# SmartLamp.net
KiCad netlist of a schematic drawn in EAGLE
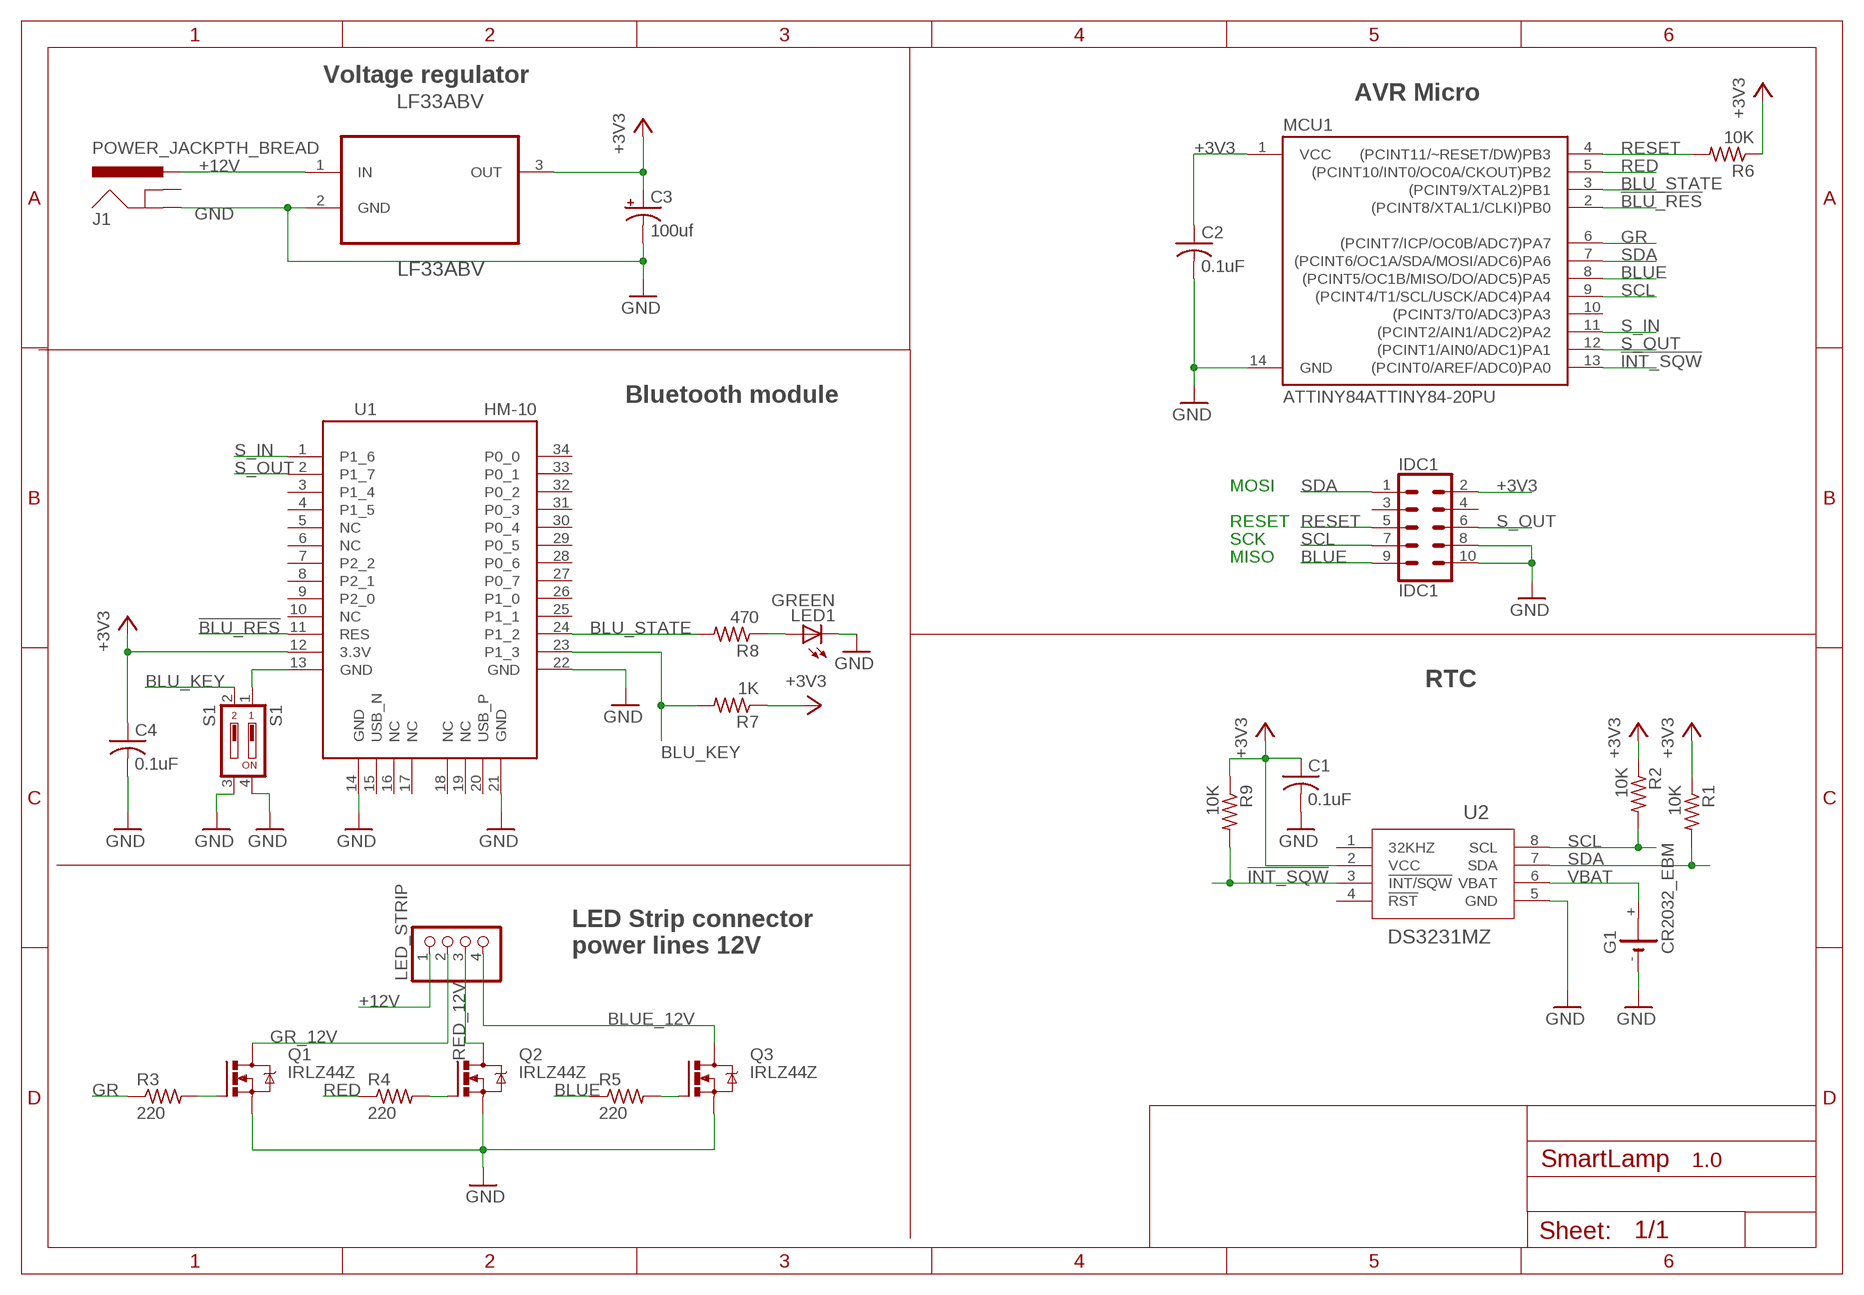
[diagram p0: schematic, sheet 1]

(export (version "E")
  (design (tool "Eeschema 10.0.6"))
  (components
    (comp (ref "C1")
      (value "0.1uF")
      (footprint "eagle-import:C025-024X044")
      (libsource (lib "eagle-import") (part "C-US025-024X044"))
    )
    (comp (ref "C2")
      (value "0.1uF")
      (footprint "eagle-import:C025-024X044")
      (libsource (lib "eagle-import") (part "C-US025-024X044"))
    )
    (comp (ref "C3")
      (value "100uf")
      (footprint "eagle-import:CPOL-RADIAL-10UF-25V")
      (libsource (lib "eagle-import") (part "CAP_POLPTH2"))
    )
    (comp (ref "C4")
      (value "0.1uF")
      (footprint "eagle-import:C025-024X044")
      (libsource (lib "eagle-import") (part "C-US025-024X044"))
    )
    (comp (ref "G1")
      (value "CR2032_EBM")
      (footprint "eagle-import:CR2032_EBM")
      (libsource (lib "eagle-import") (part "CR2032_EBM"))
    )
    (comp (ref "IDC1")
      (value "IDC1")
      (footprint "eagle-import:2X5-SHROUDED")
      (libsource (lib "eagle-import") (part "CONN_05X2SHD"))
    )
    (comp (ref "J1")
      (value "POWER_JACKPTH_BREAD")
      (footprint "eagle-import:POWER_JACK_PTH_BREAD")
      (libsource (lib "eagle-import") (part "POWER_JACKPTH_BREAD"))
    )
    (comp (ref "LED1")
      (value "GREEN")
      (footprint "eagle-import:LED3MM")
      (libsource (lib "eagle-import") (part "LED3MM"))
    )
    (comp (ref "LED_STRIP")
      (value "PINHD-1X4")
      (footprint "eagle-import:1X04")
      (libsource (lib "eagle-import") (part "PINHD-1X4"))
    )
    (comp (ref "LF33ABV")
      (value "LF33ABV")
      (footprint "eagle-import:TO254P450X1020X1935-3P")
      (libsource (lib "eagle-import") (part "LF33ABV"))
    )
    (comp (ref "MCU1")
      (value "ATTINY84ATTINY84-20PU")
      (footprint "eagle-import:DIL14")
      (libsource (lib "eagle-import") (part "ATTINY84ATTINY84-20PU"))
    )
    (comp (ref "Q1")
      (value "IRLZ44Z")
      (footprint "eagle-import:TO220BH")
      (libsource (lib "eagle-import") (part "IRLZ44Z"))
    )
    (comp (ref "Q2")
      (value "IRLZ44Z")
      (footprint "eagle-import:TO220BH")
      (libsource (lib "eagle-import") (part "IRLZ44Z"))
    )
    (comp (ref "Q3")
      (value "IRLZ44Z")
      (footprint "eagle-import:TO220BH")
      (libsource (lib "eagle-import") (part "IRLZ44Z"))
    )
    (comp (ref "R1")
      (value "10K")
      (footprint "eagle-import:0309_12")
      (libsource (lib "eagle-import") (part "R-US_0309/12"))
    )
    (comp (ref "R2")
      (value "10K")
      (footprint "eagle-import:0309_12")
      (libsource (lib "eagle-import") (part "R-US_0309/12"))
    )
    (comp (ref "R3")
      (value "220")
      (footprint "eagle-import:0207_10")
      (libsource (lib "eagle-import") (part "R-US_0207/10"))
    )
    (comp (ref "R4")
      (value "220")
      (footprint "eagle-import:0207_10")
      (libsource (lib "eagle-import") (part "R-US_0207/10"))
    )
    (comp (ref "R5")
      (value "220")
      (footprint "eagle-import:0207_10")
      (libsource (lib "eagle-import") (part "R-US_0207/10"))
    )
    (comp (ref "R6")
      (value "10K")
      (footprint "eagle-import:0309_12")
      (libsource (lib "eagle-import") (part "R-US_0309/12"))
    )
    (comp (ref "R7")
      (value "1K")
      (footprint "eagle-import:0207_10")
      (libsource (lib "eagle-import") (part "R-US_0207/10"))
    )
    (comp (ref "R8")
      (value "470")
      (footprint "eagle-import:0309_12")
      (libsource (lib "eagle-import") (part "R-US_0309/12"))
    )
    (comp (ref "R9")
      (value "10K")
      (footprint "eagle-import:0309_12")
      (libsource (lib "eagle-import") (part "R-US_0309/12"))
    )
    (comp (ref "S1")
      (value "S1")
      (footprint "eagle-import:SD4-02")
      (libsource (lib "eagle-import") (part "SD4-02"))
    )
    (comp (ref "U1")
      (value "HM-10")
      (footprint "eagle-import:HM-10")
      (libsource (lib "eagle-import") (part "HM-10"))
    )
    (comp (ref "U2")
      (value "DS3231MZ")
      (footprint "eagle-import:21-0041B_8")
      (libsource (lib "eagle-import") (part "DS3231MZ"))
    )
  )
  (nets
    (net (code "1") (name "+3V3") (class "Default")
      (node (ref "C1") (pin "1") (pinfunction "1_1") (pintype "passive"))
      (node (ref "C2") (pin "1") (pinfunction "1_1") (pintype "passive"))
      (node (ref "C3") (pin "1") (pinfunction "+_1") (pintype "passive"))
      (node (ref "C4") (pin "1") (pinfunction "1_1") (pintype "passive"))
      (node (ref "IDC1") (pin "2") (pinfunction "2_2") (pintype "passive"))
      (node (ref "LF33ABV") (pin "3") (pinfunction "OUT_3") (pintype "passive"))
      (node (ref "MCU1") (pin "1") (pinfunction "VCC_1") (pintype "bidirectional"))
      (node (ref "R1") (pin "1") (pinfunction "1_1") (pintype "passive"))
      (node (ref "R2") (pin "1") (pinfunction "1_1") (pintype "passive"))
      (node (ref "R6") (pin "1") (pinfunction "1_1") (pintype "passive"))
      (node (ref "R7") (pin "1") (pinfunction "1_1") (pintype "passive"))
      (node (ref "R9") (pin "1") (pinfunction "1_1") (pintype "passive"))
      (node (ref "U1") (pin "12") (pinfunction "3.3V_12") (pintype "bidirectional"))
      (node (ref "U2") (pin "2") (pinfunction "VCC_2") (pintype "power_in"))
    )
    (net (code "2") (name "/+12V") (class "Default")
      (node (ref "J1") (pin "PWR") (pinfunction "PWR_PWR") (pintype "bidirectional"))
      (node (ref "LED_STRIP") (pin "1") (pinfunction "1_1") (pintype "passive"))
      (node (ref "LF33ABV") (pin "1") (pinfunction "IN_1") (pintype "input"))
    )
    (net (code "3") (name "/BLUE") (class "Default")
      (node (ref "IDC1") (pin "9") (pinfunction "9_9") (pintype "passive"))
      (node (ref "MCU1") (pin "8") (pinfunction "(PCINT5/OC1B/MISO/DO/ADC5)PA5_8") (pintype "bidirectional"))
      (node (ref "R5") (pin "1") (pinfunction "1_1") (pintype "passive"))
    )
    (net (code "4") (name "/BLUE_12V") (class "Default")
      (node (ref "LED_STRIP") (pin "4") (pinfunction "4_4") (pintype "passive"))
      (node (ref "Q3") (pin "D") (pinfunction "D_D") (pintype "passive"))
    )
    (net (code "5") (name "/BLU_KEY") (class "Default")
      (node (ref "R7") (pin "2") (pinfunction "2_2") (pintype "passive"))
      (node (ref "S1") (pin "2") (pinfunction "2_2") (pintype "passive"))
      (node (ref "U1") (pin "23") (pinfunction "P1_3_23") (pintype "bidirectional"))
    )
    (net (code "6") (name "/BLU_STATE") (class "Default")
      (node (ref "MCU1") (pin "3") (pinfunction "(PCINT9/XTAL2)PB1_3") (pintype "bidirectional"))
      (node (ref "R8") (pin "2") (pinfunction "2_2") (pintype "passive"))
      (node (ref "U1") (pin "24") (pinfunction "P1_2_24") (pintype "bidirectional"))
    )
    (net (code "7") (name "/GR") (class "Default")
      (node (ref "MCU1") (pin "6") (pinfunction "(PCINT7/ICP/OC0B/ADC7)PA7_6") (pintype "bidirectional"))
      (node (ref "R3") (pin "1") (pinfunction "1_1") (pintype "passive"))
    )
    (net (code "8") (name "/GR_12V") (class "Default")
      (node (ref "LED_STRIP") (pin "2") (pinfunction "2_2") (pintype "passive"))
      (node (ref "Q1") (pin "D") (pinfunction "D_D") (pintype "passive"))
    )
    (net (code "9") (name "/RED") (class "Default")
      (node (ref "MCU1") (pin "5") (pinfunction "(PCINT10/INT0/OC0A/CKOUT)PB2_5") (pintype "bidirectional"))
      (node (ref "R4") (pin "1") (pinfunction "1_1") (pintype "passive"))
    )
    (net (code "10") (name "/RED_12V") (class "Default")
      (node (ref "LED_STRIP") (pin "3") (pinfunction "3_3") (pintype "passive"))
      (node (ref "Q2") (pin "D") (pinfunction "D_D") (pintype "passive"))
    )
    (net (code "11") (name "/RESET") (class "Default")
      (node (ref "IDC1") (pin "5") (pinfunction "5_5") (pintype "passive"))
      (node (ref "MCU1") (pin "4") (pinfunction "(PCINT11/~{RESET/DW})PB3_4") (pintype "bidirectional"))
      (node (ref "R6") (pin "2") (pinfunction "2_2") (pintype "passive"))
    )
    (net (code "12") (name "/SCL") (class "Default")
      (node (ref "IDC1") (pin "7") (pinfunction "7_7") (pintype "passive"))
      (node (ref "MCU1") (pin "9") (pinfunction "(PCINT4/T1/SCL/USCK/ADC4)PA4_9") (pintype "bidirectional"))
      (node (ref "R2") (pin "2") (pinfunction "2_2") (pintype "passive"))
      (node (ref "U2") (pin "8") (pinfunction "SCL_8") (pintype "passive"))
    )
    (net (code "13") (name "/SDA") (class "Default")
      (node (ref "IDC1") (pin "1") (pinfunction "1_1") (pintype "passive"))
      (node (ref "MCU1") (pin "7") (pinfunction "(PCINT6/OC1A/SDA/MOSI/ADC6)PA6_7") (pintype "bidirectional"))
      (node (ref "R1") (pin "2") (pinfunction "2_2") (pintype "passive"))
      (node (ref "U2") (pin "7") (pinfunction "SDA_7") (pintype "passive"))
    )
    (net (code "14") (name "/S_IN") (class "Default")
      (node (ref "MCU1") (pin "11") (pinfunction "(PCINT2/AIN1/ADC2)PA2_11") (pintype "bidirectional"))
      (node (ref "U1") (pin "1") (pinfunction "P1_6_1") (pintype "bidirectional"))
    )
    (net (code "15") (name "/S_OUT") (class "Default")
      (node (ref "IDC1") (pin "6") (pinfunction "6_6") (pintype "passive"))
      (node (ref "MCU1") (pin "12") (pinfunction "(PCINT1/AIN0/ADC1)PA1_12") (pintype "bidirectional"))
      (node (ref "U1") (pin "2") (pinfunction "P1_7_2") (pintype "bidirectional"))
    )
    (net (code "16") (name "/VBAT") (class "Default")
      (node (ref "G1") (pin "+") (pinfunction "+_+") (pintype "passive"))
      (node (ref "U2") (pin "6") (pinfunction "VBAT_6") (pintype "power_in"))
    )
    (net (code "17") (name "/~{BLU_RES}") (class "Default")
      (node (ref "MCU1") (pin "2") (pinfunction "(PCINT8/XTAL1/CLKI)PB0_2") (pintype "bidirectional"))
      (node (ref "U1") (pin "11") (pinfunction "RES_11") (pintype "bidirectional"))
    )
    (net (code "18") (name "/~{INT_SQW}") (class "Default")
      (node (ref "MCU1") (pin "13") (pinfunction "(PCINT0/AREF/ADC0)PA0_13") (pintype "bidirectional"))
      (node (ref "R9") (pin "2") (pinfunction "2_2") (pintype "passive"))
      (node (ref "U2") (pin "3") (pinfunction "~{INT/SQW}_3") (pintype "passive"))
    )
    (net (code "19") (name "GND") (class "Default")
      (node (ref "C1") (pin "2") (pinfunction "2_2") (pintype "passive"))
      (node (ref "C2") (pin "2") (pinfunction "2_2") (pintype "passive"))
      (node (ref "C3") (pin "2") (pinfunction "-_2") (pintype "passive"))
      (node (ref "C4") (pin "2") (pinfunction "2_2") (pintype "passive"))
      (node (ref "G1") (pin "-") (pinfunction "-_-") (pintype "passive"))
      (node (ref "IDC1") (pin "10") (pinfunction "10_10") (pintype "passive"))
      (node (ref "IDC1") (pin "8") (pinfunction "8_8") (pintype "passive"))
      (node (ref "J1") (pin "GND") (pinfunction "GND_GND") (pintype "bidirectional"))
      (node (ref "LED1") (pin "K") (pinfunction "C_K") (pintype "passive"))
      (node (ref "LF33ABV") (pin "2") (pinfunction "GND_2") (pintype "passive"))
      (node (ref "MCU1") (pin "14") (pinfunction "GND_14") (pintype "bidirectional"))
      (node (ref "Q1") (pin "S") (pinfunction "S_S") (pintype "passive"))
      (node (ref "Q2") (pin "S") (pinfunction "S_S") (pintype "passive"))
      (node (ref "Q3") (pin "S") (pinfunction "S_S") (pintype "passive"))
      (node (ref "S1") (pin "3") (pinfunction "3_3") (pintype "passive"))
      (node (ref "S1") (pin "4") (pinfunction "4_4") (pintype "passive"))
      (node (ref "U1") (pin "14") (pinfunction "GND_14") (pintype "bidirectional"))
      (node (ref "U1") (pin "21") (pinfunction "GND_21") (pintype "bidirectional"))
      (node (ref "U1") (pin "22") (pinfunction "GND_22") (pintype "bidirectional"))
      (node (ref "U2") (pin "5") (pinfunction "GND_5") (pintype "power_in"))
    )
    (net (code "20") (name "Net-(LED1-PadA)") (class "Default")
      (node (ref "LED1") (pin "A") (pinfunction "A_A") (pintype "passive"))
      (node (ref "R8") (pin "1") (pinfunction "1_1") (pintype "passive"))
    )
    (net (code "21") (name "Net-(Q1-PadG)") (class "Default")
      (node (ref "Q1") (pin "G") (pinfunction "G_G") (pintype "passive"))
      (node (ref "R3") (pin "2") (pinfunction "2_2") (pintype "passive"))
    )
    (net (code "22") (name "Net-(Q2-PadG)") (class "Default")
      (node (ref "Q2") (pin "G") (pinfunction "G_G") (pintype "passive"))
      (node (ref "R4") (pin "2") (pinfunction "2_2") (pintype "passive"))
    )
    (net (code "23") (name "Net-(Q3-PadG)") (class "Default")
      (node (ref "Q3") (pin "G") (pinfunction "G_G") (pintype "passive"))
      (node (ref "R5") (pin "2") (pinfunction "2_2") (pintype "passive"))
    )
    (net (code "24") (name "Net-(S1-Pad1)") (class "Default")
      (node (ref "S1") (pin "1") (pinfunction "1_1") (pintype "passive"))
      (node (ref "U1") (pin "13") (pinfunction "GND_13") (pintype "bidirectional"))
    )
    (net (code "25") (name "unconnected-(IDC1-Pad3)") (class "Default")
      (node (ref "IDC1") (pin "3") (pinfunction "3_3") (pintype "passive"))
    )
    (net (code "26") (name "unconnected-(IDC1-Pad4)") (class "Default")
      (node (ref "IDC1") (pin "4") (pinfunction "4_4") (pintype "passive"))
    )
    (net (code "27") (name "unconnected-(J1-PadGNDBREAK)") (class "Default")
      (node (ref "J1") (pin "GNDBREAK") (pinfunction "GNDBREAK_GNDBREAK") (pintype "bidirectional"))
    )
    (net (code "28") (name "unconnected-(MCU1-(PCINT3{slash}T0{slash}ADC3)PA3-Pad10)") (class "Default")
      (node (ref "MCU1") (pin "10") (pinfunction "(PCINT3/T0/ADC3)PA3_10") (pintype "bidirectional"))
    )
    (net (code "29") (name "unconnected-(U1-NC-Pad5)") (class "Default")
      (node (ref "U1") (pin "5") (pinfunction "NC_5") (pintype "bidirectional"))
    )
    (net (code "30") (name "unconnected-(U1-NC-Pad6)") (class "Default")
      (node (ref "U1") (pin "6") (pinfunction "NC_6") (pintype "bidirectional"))
    )
    (net (code "31") (name "unconnected-(U1-NC-Pad10)") (class "Default")
      (node (ref "U1") (pin "10") (pinfunction "NC_10") (pintype "bidirectional"))
    )
    (net (code "32") (name "unconnected-(U1-NC-Pad16)") (class "Default")
      (node (ref "U1") (pin "16") (pinfunction "NC_16") (pintype "bidirectional"))
    )
    (net (code "33") (name "unconnected-(U1-NC-Pad17)") (class "Default")
      (node (ref "U1") (pin "17") (pinfunction "NC_17") (pintype "bidirectional"))
    )
    (net (code "34") (name "unconnected-(U1-NC-Pad18)") (class "Default")
      (node (ref "U1") (pin "18") (pinfunction "NC_18") (pintype "bidirectional"))
    )
    (net (code "35") (name "unconnected-(U1-NC-Pad19)") (class "Default")
      (node (ref "U1") (pin "19") (pinfunction "NC_19") (pintype "bidirectional"))
    )
    (net (code "36") (name "unconnected-(U1-P0_0-Pad34)") (class "Default")
      (node (ref "U1") (pin "34") (pinfunction "P0_0_34") (pintype "bidirectional"))
    )
    (net (code "37") (name "unconnected-(U1-P0_1-Pad33)") (class "Default")
      (node (ref "U1") (pin "33") (pinfunction "P0_1_33") (pintype "bidirectional"))
    )
    (net (code "38") (name "unconnected-(U1-P0_2-Pad32)") (class "Default")
      (node (ref "U1") (pin "32") (pinfunction "P0_2_32") (pintype "bidirectional"))
    )
    (net (code "39") (name "unconnected-(U1-P0_3-Pad31)") (class "Default")
      (node (ref "U1") (pin "31") (pinfunction "P0_3_31") (pintype "bidirectional"))
    )
    (net (code "40") (name "unconnected-(U1-P0_4-Pad30)") (class "Default")
      (node (ref "U1") (pin "30") (pinfunction "P0_4_30") (pintype "bidirectional"))
    )
    (net (code "41") (name "unconnected-(U1-P0_5-Pad29)") (class "Default")
      (node (ref "U1") (pin "29") (pinfunction "P0_5_29") (pintype "bidirectional"))
    )
    (net (code "42") (name "unconnected-(U1-P0_6-Pad28)") (class "Default")
      (node (ref "U1") (pin "28") (pinfunction "P0_6_28") (pintype "bidirectional"))
    )
    (net (code "43") (name "unconnected-(U1-P0_7-Pad27)") (class "Default")
      (node (ref "U1") (pin "27") (pinfunction "P0_7_27") (pintype "bidirectional"))
    )
    (net (code "44") (name "unconnected-(U1-P1_0-Pad26)") (class "Default")
      (node (ref "U1") (pin "26") (pinfunction "P1_0_26") (pintype "bidirectional"))
    )
    (net (code "45") (name "unconnected-(U1-P1_1-Pad25)") (class "Default")
      (node (ref "U1") (pin "25") (pinfunction "P1_1_25") (pintype "bidirectional"))
    )
    (net (code "46") (name "unconnected-(U1-P1_4-Pad3)") (class "Default")
      (node (ref "U1") (pin "3") (pinfunction "P1_4_3") (pintype "bidirectional"))
    )
    (net (code "47") (name "unconnected-(U1-P1_5-Pad4)") (class "Default")
      (node (ref "U1") (pin "4") (pinfunction "P1_5_4") (pintype "bidirectional"))
    )
    (net (code "48") (name "unconnected-(U1-P2_0-Pad9)") (class "Default")
      (node (ref "U1") (pin "9") (pinfunction "P2_0_9") (pintype "bidirectional"))
    )
    (net (code "49") (name "unconnected-(U1-P2_1-Pad8)") (class "Default")
      (node (ref "U1") (pin "8") (pinfunction "P2_1_8") (pintype "bidirectional"))
    )
    (net (code "50") (name "unconnected-(U1-P2_2-Pad7)") (class "Default")
      (node (ref "U1") (pin "7") (pinfunction "P2_2_7") (pintype "bidirectional"))
    )
    (net (code "51") (name "unconnected-(U1-USB_N-Pad15)") (class "Default")
      (node (ref "U1") (pin "15") (pinfunction "USB_N_15") (pintype "bidirectional"))
    )
    (net (code "52") (name "unconnected-(U1-USB_P-Pad20)") (class "Default")
      (node (ref "U1") (pin "20") (pinfunction "USB_P_20") (pintype "bidirectional"))
    )
    (net (code "53") (name "unconnected-(U2-32KHZ-Pad1)") (class "Default")
      (node (ref "U2") (pin "1") (pinfunction "32KHZ_1") (pintype "passive"))
    )
    (net (code "54") (name "unconnected-(U2-~{RST}-Pad4)") (class "Default")
      (node (ref "U2") (pin "4") (pinfunction "~{RST}_4") (pintype "passive"))
    )
  )
)
